# ProDocument_CPUCable_2023-08-07.net
KiCad netlist of a schematic drawn in EasyEDA Pro
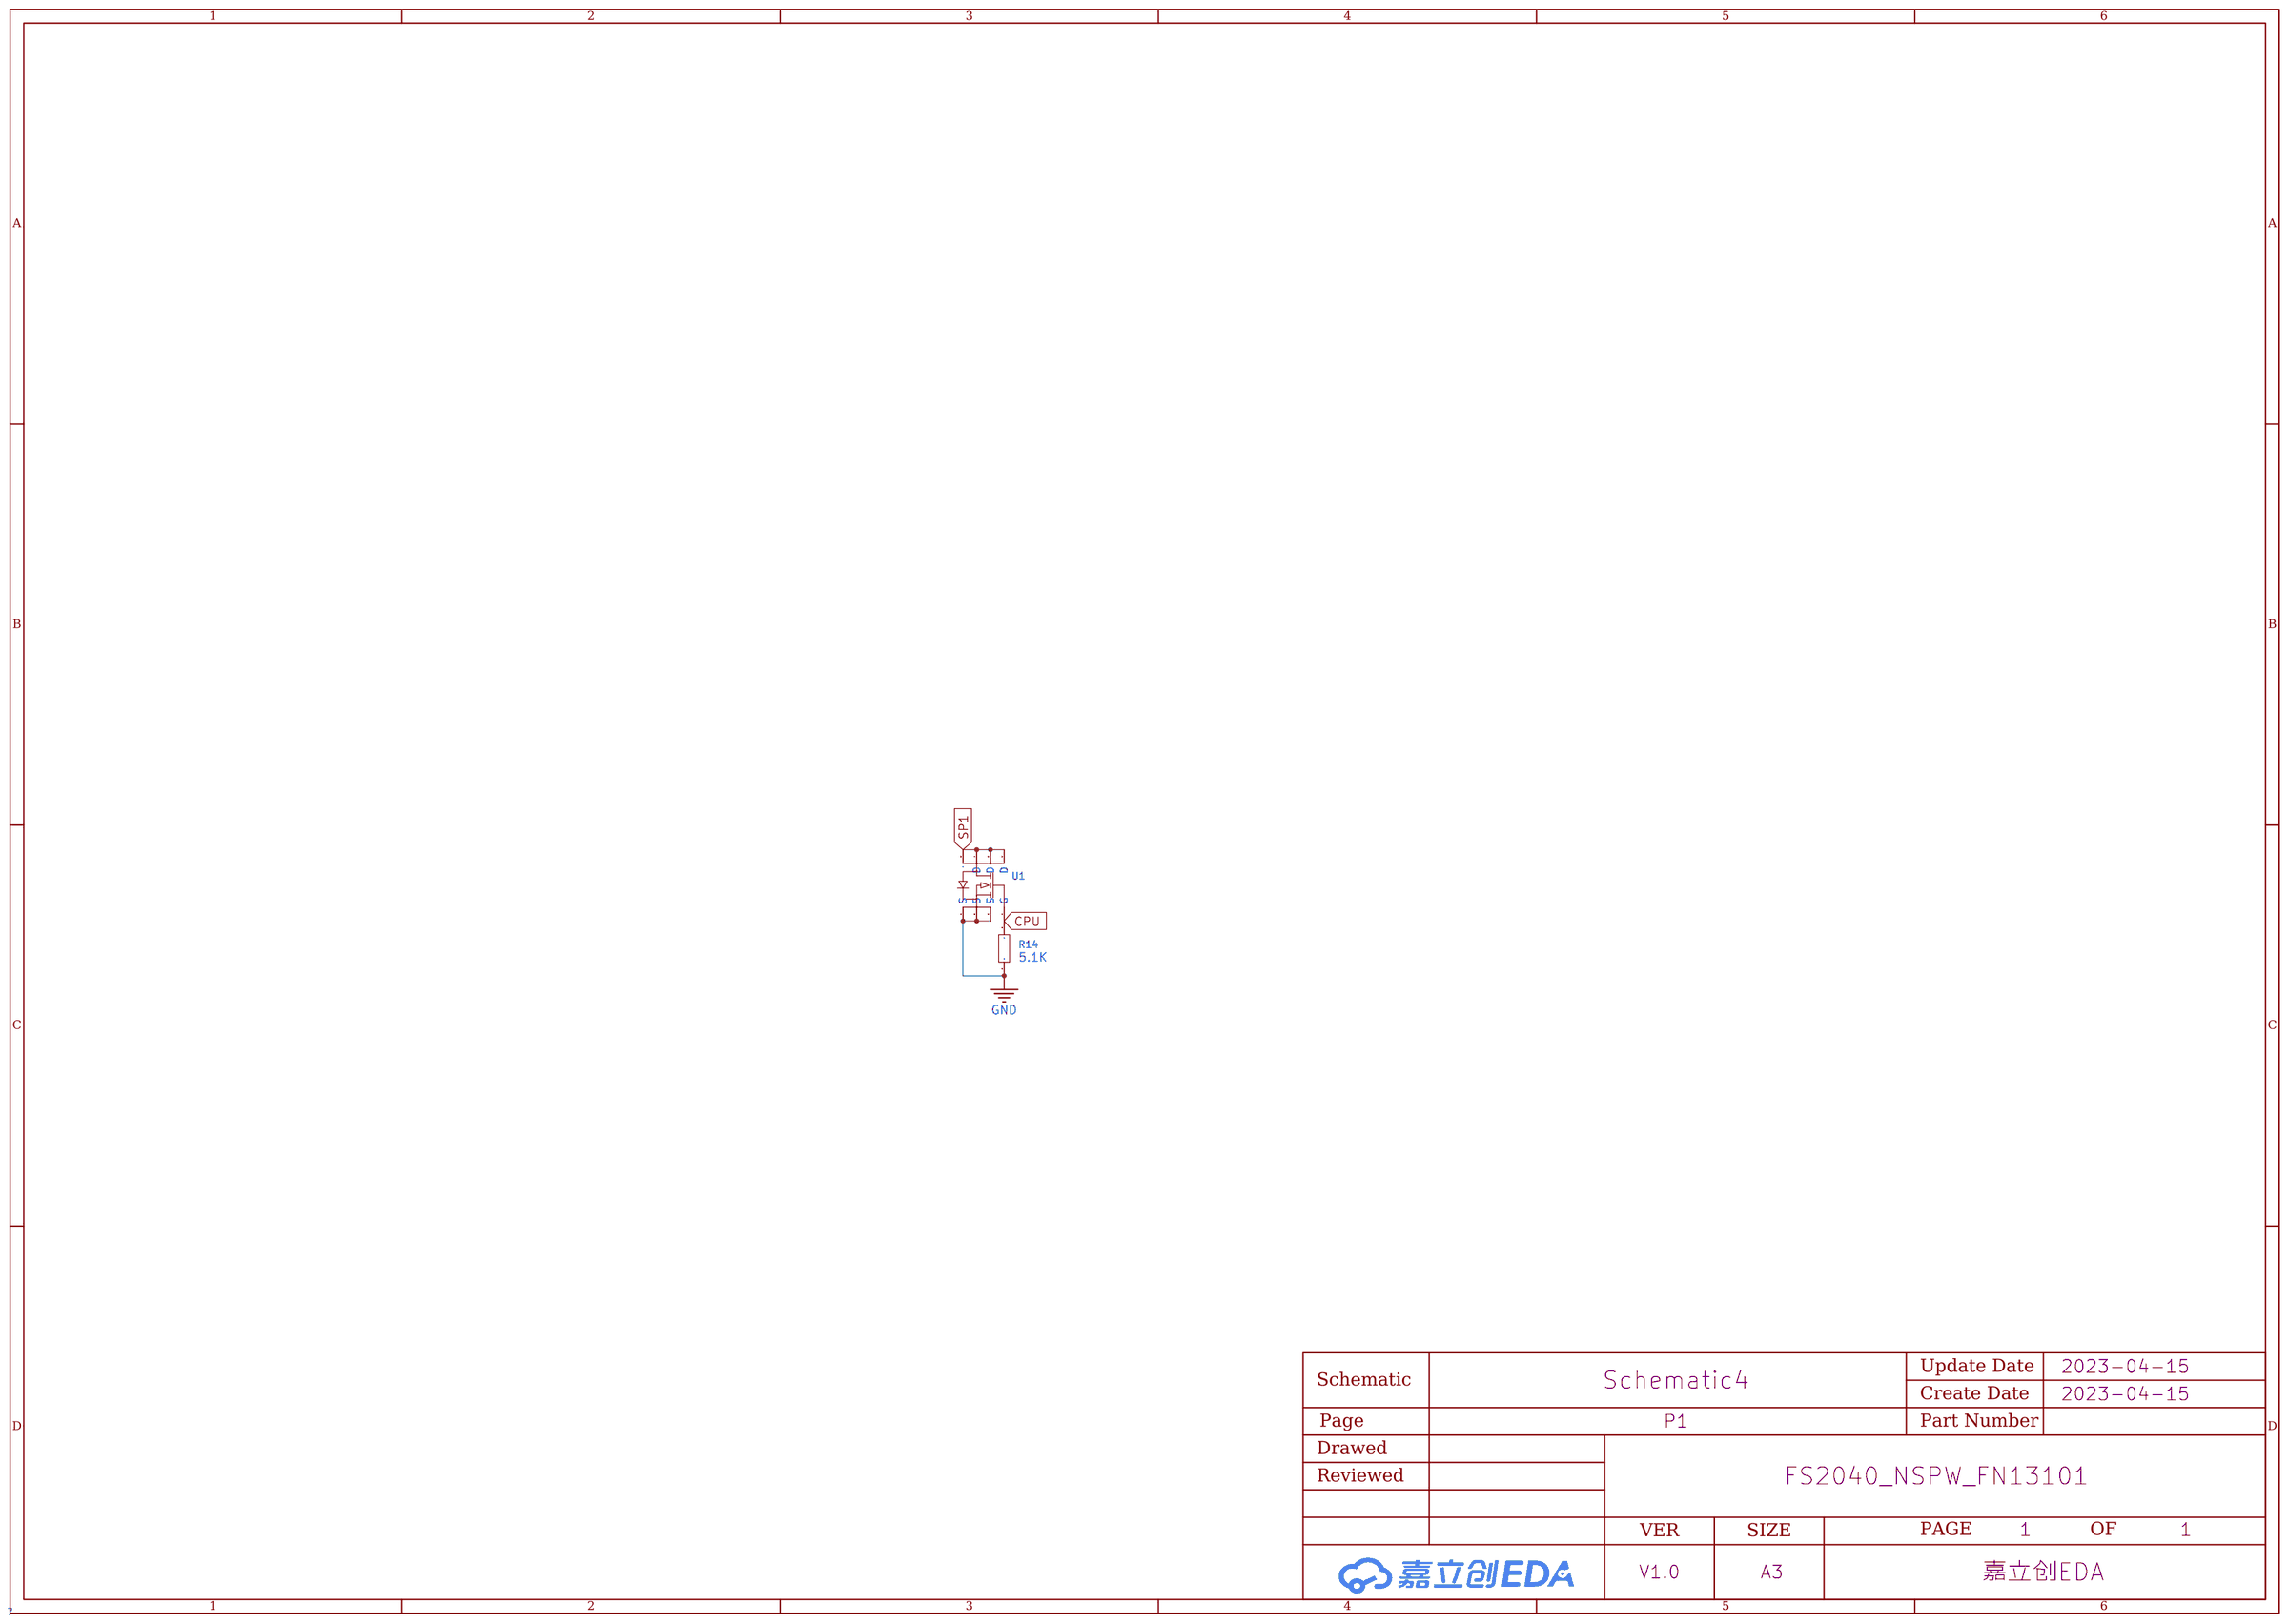
[diagram p0: schematic sheet]

(export (version "E")
  (design (tool "Eeschema 10.0.6"))
  (components
    (comp (ref "R14")
      (value "5.1K")
      (footprint "easyedapro:R0402_FS")
      (description "阻值:5.1kΩ;精度:±1%;功率:62.5mW;")
      (fields (field (name "Manufacturer Part") "RMC04025.1K1%N") (field (name "Manufacturer") "Tyohm(幸亚电阻)"))
      (libsource (lib "easyedapro") (part "RMC04025.1K1%N"))
    )
    (comp (ref "U1")
      (value "AP50N03DF")
      (footprint "easyedapro:POWERVDFN-8_L3.2-W3.1-P0.65-LS3.3-BL-1")
      (fields (field (name "Manufacturer") "APM(永源微电子)"))
      (libsource (lib "easyedapro") (part "AP50N03DF"))
    )
  )
  (nets
    (net (code "1") (name "CPU") (class "Default")
      (node (ref "R14") (pin "2") (pinfunction "2_2") (pintype "input"))
      (node (ref "U1") (pin "4") (pinfunction "G_4") (pintype "input"))
    )
    (net (code "2") (name "GND") (class "Default")
      (node (ref "R14") (pin "1") (pinfunction "1_1") (pintype "input"))
      (node (ref "U1") (pin "1") (pinfunction "S_1") (pintype "input"))
      (node (ref "U1") (pin "2") (pinfunction "S_2") (pintype "input"))
      (node (ref "U1") (pin "3") (pinfunction "S_3") (pintype "input"))
    )
    (net (code "3") (name "SP1") (class "Default")
      (node (ref "U1") (pin "5") (pinfunction "D_5") (pintype "input"))
      (node (ref "U1") (pin "6") (pinfunction "D_6") (pintype "input"))
      (node (ref "U1") (pin "7") (pinfunction "D_7") (pintype "input"))
      (node (ref "U1") (pin "8") (pinfunction "D_8") (pintype "input"))
    )
  )
)
